# eyesdrive-rev1.net
KiCad netlist of a schematic drawn in EAGLE
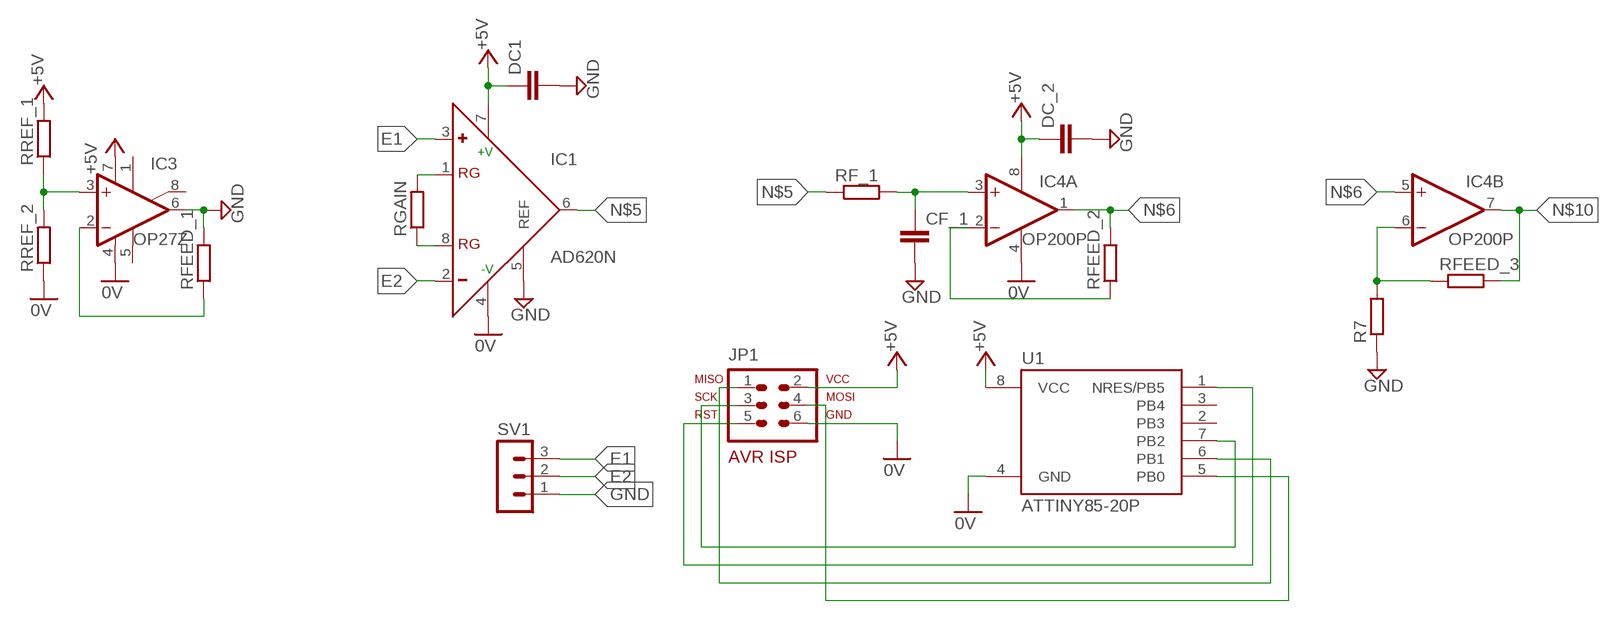
[diagram p0: schematic, sheet 1]

(export (version "E")
  (design (tool "Eeschema 10.0.6"))
  (components
    (comp (ref "CF_1")
      (value "C-EU025-025X050")
      (footprint "eagle-import:C025-025X050")
      (libsource (lib "eagle-import") (part "C-EU025-025X050"))
    )
    (comp (ref "DC1")
      (value "C-EU050-025X075")
      (footprint "eagle-import:C050-025X075")
      (libsource (lib "eagle-import") (part "C-EU050-025X075"))
    )
    (comp (ref "DC_2")
      (value "C-EU025-025X050")
      (footprint "eagle-import:C025-025X050")
      (libsource (lib "eagle-import") (part "C-EU025-025X050"))
    )
    (comp (ref "IC1")
      (value "AD620N")
      (footprint "eagle-import:DIL08")
      (fields (field (name "MF") "ALTERA CORPORATION") (field (name "MPN") "AD620AN"))
      (libsource (lib "eagle-import") (part "AD620N"))
    )
    (comp (ref "IC3")
      (value "OP27Z")
      (footprint "eagle-import:DIL08")
      (libsource (lib "eagle-import") (part "OP27Z"))
    )
    (comp (ref "IC4")
      (value "OP200P")
      (footprint "eagle-import:DIL08")
      (libsource (lib "eagle-import") (part "OP200P"))
    )
    (comp (ref "JP1")
      (value "AVR-ISP-6VERT")
      (footprint "eagle-import:AVR-ISP-6")
      (libsource (lib "eagle-import") (part "AVR-ISP-6VERT"))
    )
    (comp (ref "R7")
      (value "R-EU_0207/7")
      (footprint "eagle-import:0207_7")
      (libsource (lib "eagle-import") (part "R-EU_0207/7"))
    )
    (comp (ref "RFEED_1")
      (value "R-EU_0207/7")
      (footprint "eagle-import:0207_7")
      (libsource (lib "eagle-import") (part "R-EU_0207/7"))
    )
    (comp (ref "RFEED_2")
      (value "R-EU_0207/7")
      (footprint "eagle-import:0207_7")
      (libsource (lib "eagle-import") (part "R-EU_0207/7"))
    )
    (comp (ref "RFEED_3")
      (value "R-EU_0207/7")
      (footprint "eagle-import:0207_7")
      (libsource (lib "eagle-import") (part "R-EU_0207/7"))
    )
    (comp (ref "RF_1")
      (value "R-EU_0207/7")
      (footprint "eagle-import:0207_7")
      (libsource (lib "eagle-import") (part "R-EU_0207/7"))
    )
    (comp (ref "RGAIN")
      (value "R-EU_0207/7")
      (footprint "eagle-import:0207_7")
      (libsource (lib "eagle-import") (part "R-EU_0207/7"))
    )
    (comp (ref "RREF_1")
      (value "R-EU_0207/7")
      (footprint "eagle-import:0207_7")
      (libsource (lib "eagle-import") (part "R-EU_0207/7"))
    )
    (comp (ref "RREF_2")
      (value "R-EU_0207/7")
      (footprint "eagle-import:0207_7")
      (libsource (lib "eagle-import") (part "R-EU_0207/7"))
    )
    (comp (ref "SV1")
      (value "MA03-1")
      (footprint "eagle-import:MA03-1")
      (libsource (lib "eagle-import") (part "MA03-1"))
    )
    (comp (ref "U1")
      (value "ATTINY85-20P")
      (footprint "eagle-import:PDIP08_300MIL")
      (libsource (lib "eagle-import") (part "ATTINY85P-20"))
    )
  )
  (nets
    (net (code "1") (name "+5V") (class "Default")
      (node (ref "DC1") (pin "1") (pinfunction "1_1") (pintype "passive"))
      (node (ref "DC_2") (pin "1") (pinfunction "1_1") (pintype "passive"))
      (node (ref "IC1") (pin "7") (pinfunction "+V_7") (pintype "power_in"))
      (node (ref "IC3") (pin "7") (pinfunction "V+_7") (pintype "power_in"))
      (node (ref "IC4") (pin "8") (pinfunction "V+_8") (pintype "power_in"))
      (node (ref "JP1") (pin "2") (pinfunction "2_2") (pintype "passive"))
      (node (ref "RREF_1") (pin "2") (pinfunction "2_2") (pintype "passive"))
      (node (ref "U1") (pin "8") (pinfunction "VCC_8") (pintype "power_in"))
    )
    (net (code "2") (name "0V") (class "Default")
      (node (ref "IC1") (pin "4") (pinfunction "-V_4") (pintype "power_in"))
      (node (ref "IC3") (pin "4") (pinfunction "V-_4") (pintype "power_in"))
      (node (ref "IC4") (pin "4") (pinfunction "V-_4") (pintype "power_in"))
      (node (ref "JP1") (pin "6") (pinfunction "6_6") (pintype "passive"))
      (node (ref "RREF_2") (pin "1") (pinfunction "1_1") (pintype "passive"))
      (node (ref "U1") (pin "4") (pinfunction "GND_4") (pintype "power_in"))
    )
    (net (code "3") (name "E1") (class "Default")
      (node (ref "IC1") (pin "3") (pinfunction "+_3") (pintype "input"))
      (node (ref "SV1") (pin "3") (pinfunction "3_3") (pintype "passive"))
    )
    (net (code "4") (name "E2") (class "Default")
      (node (ref "IC1") (pin "2") (pinfunction "-_2") (pintype "input"))
      (node (ref "SV1") (pin "2") (pinfunction "2_2") (pintype "passive"))
    )
    (net (code "5") (name "GND") (class "Default")
      (node (ref "CF_1") (pin "2") (pinfunction "2_2") (pintype "passive"))
      (node (ref "DC1") (pin "2") (pinfunction "2_2") (pintype "passive"))
      (node (ref "DC_2") (pin "2") (pinfunction "2_2") (pintype "passive"))
      (node (ref "IC1") (pin "5") (pinfunction "REF_5") (pintype "passive"))
      (node (ref "IC3") (pin "6") (pinfunction "OUT_6") (pintype "output"))
      (node (ref "R7") (pin "1") (pinfunction "1_1") (pintype "passive"))
      (node (ref "RFEED_1") (pin "2") (pinfunction "2_2") (pintype "passive"))
      (node (ref "SV1") (pin "1") (pinfunction "1_1") (pintype "passive"))
    )
    (net (code "6") (name "N$5") (class "Default")
      (node (ref "IC1") (pin "6") (pinfunction "OUT_6") (pintype "output"))
      (node (ref "RF_1") (pin "1") (pinfunction "1_1") (pintype "passive"))
    )
    (net (code "7") (name "N$6") (class "Default")
      (node (ref "IC4") (pin "1") (pinfunction "OUT_1") (pintype "output"))
      (node (ref "IC4") (pin "5") (pinfunction "+IN_5") (pintype "input"))
      (node (ref "RFEED_2") (pin "2") (pinfunction "2_2") (pintype "passive"))
    )
    (net (code "8") (name "N$10") (class "Default")
      (node (ref "IC4") (pin "7") (pinfunction "OUT_7") (pintype "output"))
      (node (ref "RFEED_3") (pin "2") (pinfunction "2_2") (pintype "passive"))
    )
    (net (code "9") (name "Net-(IC1-RG-Pad1)") (class "Default")
      (node (ref "IC1") (pin "1") (pinfunction "RG_1") (pintype "passive"))
      (node (ref "RGAIN") (pin "2") (pinfunction "2_2") (pintype "passive"))
    )
    (net (code "10") (name "Net-(IC1-RG-Pad8)") (class "Default")
      (node (ref "IC1") (pin "8") (pinfunction "RG_8") (pintype "passive"))
      (node (ref "RGAIN") (pin "1") (pinfunction "1_1") (pintype "passive"))
    )
    (net (code "11") (name "Net-(IC3-+IN)") (class "Default")
      (node (ref "IC3") (pin "3") (pinfunction "+IN_3") (pintype "input"))
      (node (ref "RREF_1") (pin "1") (pinfunction "1_1") (pintype "passive"))
      (node (ref "RREF_2") (pin "2") (pinfunction "2_2") (pintype "passive"))
    )
    (net (code "12") (name "Net-(IC3--IN)") (class "Default")
      (node (ref "IC3") (pin "2") (pinfunction "-IN_2") (pintype "input"))
      (node (ref "RFEED_1") (pin "1") (pinfunction "1_1") (pintype "passive"))
    )
    (net (code "13") (name "Net-(IC4A-+IN)") (class "Default")
      (node (ref "CF_1") (pin "1") (pinfunction "1_1") (pintype "passive"))
      (node (ref "IC4") (pin "3") (pinfunction "+IN_3") (pintype "input"))
      (node (ref "RF_1") (pin "2") (pinfunction "2_2") (pintype "passive"))
    )
    (net (code "14") (name "Net-(IC4A--IN)") (class "Default")
      (node (ref "IC4") (pin "2") (pinfunction "-IN_2") (pintype "input"))
      (node (ref "RFEED_2") (pin "1") (pinfunction "1_1") (pintype "passive"))
    )
    (net (code "15") (name "Net-(IC4B--IN)") (class "Default")
      (node (ref "IC4") (pin "6") (pinfunction "-IN_6") (pintype "input"))
      (node (ref "R7") (pin "2") (pinfunction "2_2") (pintype "passive"))
      (node (ref "RFEED_3") (pin "1") (pinfunction "1_1") (pintype "passive"))
    )
    (net (code "16") (name "Net-(U1-NRES{slash}PB5)") (class "Default")
      (node (ref "JP1") (pin "5") (pinfunction "5_5") (pintype "passive"))
      (node (ref "U1") (pin "1") (pinfunction "NRES/PB5_1") (pintype "bidirectional"))
    )
    (net (code "17") (name "Net-(U1-PB0)") (class "Default")
      (node (ref "JP1") (pin "4") (pinfunction "4_4") (pintype "passive"))
      (node (ref "U1") (pin "5") (pinfunction "PB0_5") (pintype "bidirectional"))
    )
    (net (code "18") (name "Net-(U1-PB1)") (class "Default")
      (node (ref "JP1") (pin "1") (pinfunction "1_1") (pintype "passive"))
      (node (ref "U1") (pin "6") (pinfunction "PB1_6") (pintype "bidirectional"))
    )
    (net (code "19") (name "Net-(U1-PB2)") (class "Default")
      (node (ref "JP1") (pin "3") (pinfunction "3_3") (pintype "passive"))
      (node (ref "U1") (pin "7") (pinfunction "PB2_7") (pintype "bidirectional"))
    )
    (net (code "20") (name "unconnected-(IC3-ON1-Pad1)") (class "Default")
      (node (ref "IC3") (pin "1") (pinfunction "ON1_1") (pintype "passive"))
    )
    (net (code "21") (name "unconnected-(IC3-ON2-Pad8)") (class "Default")
      (node (ref "IC3") (pin "8") (pinfunction "ON2_8") (pintype "passive"))
    )
    (net (code "22") (name "unconnected-(IC3-OPT-Pad5)") (class "Default")
      (node (ref "IC3") (pin "5") (pinfunction "OPT_5") (pintype "passive"))
    )
    (net (code "23") (name "unconnected-(U1-PB3-Pad2)") (class "Default")
      (node (ref "U1") (pin "2") (pinfunction "PB3_2") (pintype "bidirectional"))
    )
    (net (code "24") (name "unconnected-(U1-PB4-Pad3)") (class "Default")
      (node (ref "U1") (pin "3") (pinfunction "PB4_3") (pintype "bidirectional"))
    )
  )
)
